# nguyenli.net
KiCad netlist of a schematic drawn in Altium Designer
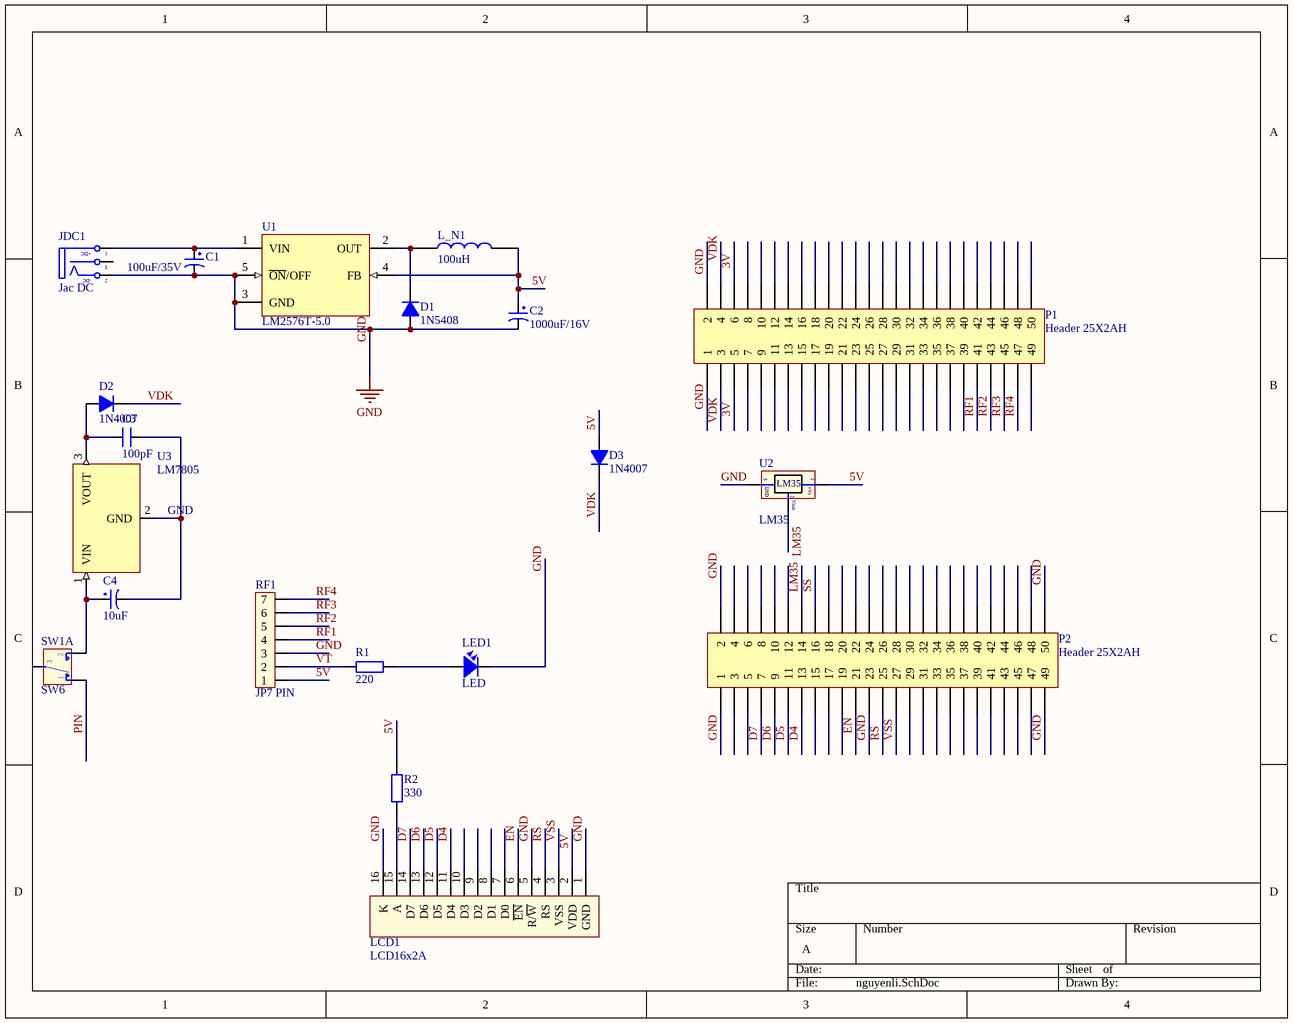
[diagram p0: nguyenli.SchDoc]

(export (version "E")
  (design (tool "Eeschema 10.0.6"))
  (components
    (comp (ref "C1")
      (value "100uF/35V")
      (footprint "CP1.5/3.4")
      (description "Cap 100uF/35V - 470uF/16V")
      (libsource (lib "syhaunguyen") (part "CP3"))
    )
    (comp (ref "C2")
      (value "1000uF/16V")
      (footprint "CP1.5/3.4")
      (description "Cap 1000uF/16V - 220uF/50V")
      (libsource (lib "syhaunguyen") (part "CP4"))
    )
    (comp (ref "C3")
      (value "100pF")
      (footprint "CN1")
      (description "Cap np  1pF - 472pF")
      (libsource (lib "Cty1") (part "CN1"))
    )
    (comp (ref "C4")
      (value "10uF")
      (footprint "CP1/2")
      (description "Cap P  0,1uF < 22uF , 16 - 50V")
      (libsource (lib "Cty1") (part "CP1"))
    )
    (comp (ref "D1")
      (value "1N5408")
      (footprint "D5A")
      (description "Diode 5A")
      (libsource (lib "syhaunguyen") (part "D5A"))
    )
    (comp (ref "D2")
      (value "1N4007")
      (footprint "D1A")
      (description "Diode 1A")
      (libsource (lib "Cty1") (part "D1A"))
    )
    (comp (ref "D3")
      (value "1N4007")
      (footprint "D1A")
      (description "Diode 1A")
      (libsource (lib "Cty1") (part "D1A"))
    )
    (comp (ref "JDC1")
      (value "Jac DC")
      (footprint "DC-IN")
      (description "Jac DC input")
      (libsource (lib "Cty1") (part "DCIN"))
    )
    (comp (ref "LCD1")
      (value "LCD16x2A")
      (footprint "LCD16X2")
      (description "LCD dipslay 16 char, 2 line")
      (libsource (lib "Cty1") (part "LCD16x2"))
    )
    (comp (ref "LED1")
      (value "LED")
      (footprint "LED-3")
      (description "LED Single colour Green and Red")
      (libsource (lib "syhaunguyen") (part "LED"))
    )
    (comp (ref "L_N1") (value "100uH") (footprint "100UH") (libsource (lib "Cty1") (part "INDUCTOR1")))
    (comp (ref "P1")
      (value "Header 25X2AH")
      (footprint "HDR2X25")
      (description "Header, 25-Pin, Dual row")
      (fields (field (name "PUBLISHER") "Altium Limited"))
      (libsource (lib "Cty1") (part "Header 25X2AH"))
    )
    (comp (ref "P2")
      (value "Header 25X2AH")
      (footprint "HDR2X25")
      (description "Header, 25-Pin, Dual row")
      (fields (field (name "PUBLISHER") "Altium Limited"))
      (libsource (lib "Cty1") (part "Header 25X2AH"))
    )
    (comp (ref "R1")
      (value "220")
      (footprint "R1/4W")
      (description "Resistor 1/4W")
      (libsource (lib "Cty1") (part "R1/4W"))
    )
    (comp (ref "R2")
      (value "330")
      (footprint "R1/4W")
      (description "Resistor 1/4W")
      (libsource (lib "Cty1") (part "R1/4W"))
    )
    (comp (ref "RF1") (value "JP7 PIN") (footprint "JP7") (libsource (lib "Cty1") (part "JP7")))
    (comp (ref "SW1")
      (value "SW6")
      (footprint "SW6")
      (description "SW-DTDP - 6 Pin")
      (libsource (lib "Cty1") (part "SW6"))
    )
    (comp (ref "U1")
      (value "LM2576T-5.0")
      (footprint "LM2576t")
      (description "SIMPLE SWITCHER; 3A Step-Down Voltage Regulator")
      (fields
        (field (name "MANUFACTURER") "National Semiconductor")
        (field (name "DIGIKEYPARTNUMBER") "LM2576T-5.0-ND")
        (field (name "PUBLISHER") "Altium Limited")
      )
      (libsource (lib "Cty1") (part "LM2576T-5.0"))
    )
    (comp (ref "U2")
      (value "LM35")
      (footprint "QTO-92")
      (description "Teminal")
      (libsource (lib "Cty1") (part "LM35"))
    )
    (comp (ref "U3")
      (value "LM7805")
      (footprint "QTO-220H3")
      (description "TO-220")
      (libsource (lib "Cty1") (part "LM7805"))
    )
  )
  (nets
    (net (code "1") (name "/3V") (class "Default")
      (node (ref "P1") (pin "5") (pinfunction "5_5") (pintype "passive"))
      (node (ref "P1") (pin "6") (pinfunction "6_6") (pintype "passive"))
    )
    (net (code "2") (name "/5V") (class "Default")
      (node (ref "C2") (pin "1") (pinfunction "1_1") (pintype "passive"))
      (node (ref "D3") (pin "1") (pinfunction "A_1") (pintype "passive"))
      (node (ref "LCD1") (pin "2") (pinfunction "VDD_2") (pintype "passive"))
      (node (ref "L_N1") (pin "2") (pinfunction "2_2") (pintype "passive"))
      (node (ref "R2") (pin "2") (pinfunction "2_2") (pintype "passive"))
      (node (ref "RF1") (pin "1") (pinfunction "1_1") (pintype "passive"))
      (node (ref "U1") (pin "4") (pinfunction "FB_4") (pintype "input"))
      (node (ref "U2") (pin "1") (pinfunction "+Vs_1") (pintype "passive"))
    )
    (net (code "3") (name "/D4") (class "Default")
      (node (ref "LCD1") (pin "11") (pinfunction "D4_11") (pintype "passive"))
      (node (ref "P2") (pin "13") (pinfunction "13_13") (pintype "passive"))
    )
    (net (code "4") (name "/D5") (class "Default")
      (node (ref "LCD1") (pin "12") (pinfunction "D5_12") (pintype "passive"))
      (node (ref "P2") (pin "11") (pinfunction "11_11") (pintype "passive"))
    )
    (net (code "5") (name "/D6") (class "Default")
      (node (ref "LCD1") (pin "13") (pinfunction "D6_13") (pintype "passive"))
      (node (ref "P2") (pin "9") (pinfunction "9_9") (pintype "passive"))
    )
    (net (code "6") (name "/D7") (class "Default")
      (node (ref "LCD1") (pin "14") (pinfunction "D7_14") (pintype "passive"))
      (node (ref "P2") (pin "7") (pinfunction "7_7") (pintype "passive"))
    )
    (net (code "7") (name "/EN") (class "Default")
      (node (ref "LCD1") (pin "6") (pinfunction "~{EN}_6") (pintype "passive"))
      (node (ref "P2") (pin "21") (pinfunction "21_21") (pintype "passive"))
    )
    (net (code "8") (name "/LM35") (class "Default")
      (node (ref "P2") (pin "14") (pinfunction "14_14") (pintype "passive"))
      (node (ref "U2") (pin "2") (pinfunction "Vout_2") (pintype "passive"))
    )
    (net (code "9") (name "/PIN") (class "Default")
      (node (ref "SW1") (pin "1") (pinfunction "1_1") (pintype "passive"))
    )
    (net (code "10") (name "/RF1") (class "Default")
      (node (ref "P1") (pin "41") (pinfunction "41_41") (pintype "passive"))
      (node (ref "RF1") (pin "4") (pinfunction "4_4") (pintype "passive"))
    )
    (net (code "11") (name "/RF2") (class "Default")
      (node (ref "P1") (pin "43") (pinfunction "43_43") (pintype "passive"))
      (node (ref "RF1") (pin "5") (pinfunction "5_5") (pintype "passive"))
    )
    (net (code "12") (name "/RF3") (class "Default")
      (node (ref "P1") (pin "45") (pinfunction "45_45") (pintype "passive"))
      (node (ref "RF1") (pin "6") (pinfunction "6_6") (pintype "passive"))
    )
    (net (code "13") (name "/RF4") (class "Default")
      (node (ref "P1") (pin "47") (pinfunction "47_47") (pintype "passive"))
      (node (ref "RF1") (pin "7") (pinfunction "7_7") (pintype "passive"))
    )
    (net (code "14") (name "/RS") (class "Default")
      (node (ref "LCD1") (pin "4") (pinfunction "RS_4") (pintype "passive"))
      (node (ref "P2") (pin "25") (pinfunction "25_25") (pintype "passive"))
    )
    (net (code "15") (name "/SS") (class "Default")
      (node (ref "P2") (pin "16") (pinfunction "16_16") (pintype "passive"))
    )
    (net (code "16") (name "/VDK") (class "Default")
      (node (ref "D2") (pin "2") (pinfunction "K_2") (pintype "passive"))
      (node (ref "D3") (pin "2") (pinfunction "K_2") (pintype "passive"))
      (node (ref "P1") (pin "3") (pinfunction "3_3") (pintype "passive"))
      (node (ref "P1") (pin "4") (pinfunction "4_4") (pintype "passive"))
    )
    (net (code "17") (name "/VSS") (class "Default")
      (node (ref "LCD1") (pin "3") (pinfunction "VSS_3") (pintype "passive"))
      (node (ref "P2") (pin "27") (pinfunction "27_27") (pintype "passive"))
    )
    (net (code "18") (name "/VT") (class "Default")
      (node (ref "R1") (pin "2") (pinfunction "2_2") (pintype "passive"))
      (node (ref "RF1") (pin "2") (pinfunction "2_2") (pintype "passive"))
    )
    (net (code "19") (name "GND") (class "Default")
      (node (ref "C1") (pin "2") (pinfunction "2_2") (pintype "passive"))
      (node (ref "C2") (pin "2") (pinfunction "2_2") (pintype "passive"))
      (node (ref "D1") (pin "1") (pinfunction "A_1") (pintype "passive"))
      (node (ref "JDC1") (pin "2") (pinfunction "TN_2") (pintype "passive"))
      (node (ref "LCD1") (pin "1") (pinfunction "GND_1") (pintype "passive"))
      (node (ref "LCD1") (pin "16") (pinfunction "K_16") (pintype "passive"))
      (node (ref "LCD1") (pin "5") (pinfunction "R/~{W}_5") (pintype "passive"))
      (node (ref "LED1") (pin "2") (pinfunction "2_2") (pintype "passive"))
      (node (ref "P1") (pin "1") (pinfunction "1_1") (pintype "passive"))
      (node (ref "P1") (pin "2") (pinfunction "2_2") (pintype "passive"))
      (node (ref "P2") (pin "1") (pinfunction "1_1") (pintype "passive"))
      (node (ref "P2") (pin "2") (pinfunction "2_2") (pintype "passive"))
      (node (ref "P2") (pin "23") (pinfunction "23_23") (pintype "passive"))
      (node (ref "P2") (pin "49") (pinfunction "49_49") (pintype "passive"))
      (node (ref "P2") (pin "50") (pinfunction "50_50") (pintype "passive"))
      (node (ref "RF1") (pin "3") (pinfunction "3_3") (pintype "passive"))
      (node (ref "U1") (pin "3") (pinfunction "GND_3") (pintype "power_in"))
      (node (ref "U1") (pin "5") (pinfunction "~{ON}/OFF_5") (pintype "input"))
      (node (ref "U2") (pin "3") (pinfunction "-_3") (pintype "passive"))
    )
    (net (code "20") (name "Net-(D1-K)") (class "Default")
      (node (ref "D1") (pin "2") (pinfunction "K_2") (pintype "passive"))
      (node (ref "L_N1") (pin "1") (pinfunction "1_1") (pintype "passive"))
      (node (ref "U1") (pin "2") (pinfunction "OUT_2") (pintype "power_in"))
    )
    (net (code "21") (name "Net-(D2-A)") (class "Default")
      (node (ref "C3") (pin "1") (pinfunction "1_1") (pintype "passive"))
      (node (ref "D2") (pin "1") (pinfunction "A_1") (pintype "passive"))
      (node (ref "U3") (pin "3") (pinfunction "VOUT_3") (pintype "output"))
    )
    (net (code "22") (name "Net-(JDC1-T)") (class "Default")
      (node (ref "C1") (pin "1") (pinfunction "1_1") (pintype "passive"))
      (node (ref "JDC1") (pin "1") (pinfunction "T_1") (pintype "passive"))
      (node (ref "U1") (pin "1") (pinfunction "VIN_1") (pintype "power_in"))
    )
    (net (code "23") (name "Net-(LCD1-A)") (class "Default")
      (node (ref "LCD1") (pin "15") (pinfunction "A_15") (pintype "passive"))
      (node (ref "R2") (pin "1") (pinfunction "1_1") (pintype "passive"))
    )
    (net (code "24") (name "Net-(LED1-Pad1)") (class "Default")
      (node (ref "LED1") (pin "1") (pinfunction "1_1") (pintype "passive"))
      (node (ref "R1") (pin "1") (pinfunction "1_1") (pintype "passive"))
    )
    (net (code "25") (name "Net-(U3-GND)") (class "Default")
      (node (ref "C3") (pin "2") (pinfunction "2_2") (pintype "passive"))
      (node (ref "C4") (pin "2") (pinfunction "2_2") (pintype "passive"))
      (node (ref "U3") (pin "2") (pinfunction "GND_2") (pintype "power_in"))
    )
    (net (code "26") (name "Net-(U3-VIN)") (class "Default")
      (node (ref "C4") (pin "1") (pinfunction "1_1") (pintype "passive"))
      (node (ref "SW1") (pin "2") (pinfunction "2_2") (pintype "passive"))
      (node (ref "U3") (pin "1") (pinfunction "VIN_1") (pintype "input"))
    )
    (net (code "27") (name "unconnected-(JDC1-S-Pad3)") (class "Default")
      (node (ref "JDC1") (pin "3") (pinfunction "S_3") (pintype "power_in"))
    )
    (net (code "28") (name "unconnected-(LCD1-D0-Pad7)") (class "Default")
      (node (ref "LCD1") (pin "7") (pinfunction "D0_7") (pintype "passive"))
    )
    (net (code "29") (name "unconnected-(LCD1-D1-Pad8)") (class "Default")
      (node (ref "LCD1") (pin "8") (pinfunction "D1_8") (pintype "passive"))
    )
    (net (code "30") (name "unconnected-(LCD1-D2-Pad9)") (class "Default")
      (node (ref "LCD1") (pin "9") (pinfunction "D2_9") (pintype "passive"))
    )
    (net (code "31") (name "unconnected-(LCD1-D3-Pad10)") (class "Default")
      (node (ref "LCD1") (pin "10") (pinfunction "D3_10") (pintype "passive"))
    )
    (net (code "32") (name "unconnected-(P1-Pad7)") (class "Default")
      (node (ref "P1") (pin "7") (pinfunction "7_7") (pintype "passive"))
    )
    (net (code "33") (name "unconnected-(P1-Pad8)") (class "Default")
      (node (ref "P1") (pin "8") (pinfunction "8_8") (pintype "passive"))
    )
    (net (code "34") (name "unconnected-(P1-Pad9)") (class "Default")
      (node (ref "P1") (pin "9") (pinfunction "9_9") (pintype "passive"))
    )
    (net (code "35") (name "unconnected-(P1-Pad10)") (class "Default")
      (node (ref "P1") (pin "10") (pinfunction "10_10") (pintype "passive"))
    )
    (net (code "36") (name "unconnected-(P1-Pad11)") (class "Default")
      (node (ref "P1") (pin "11") (pinfunction "11_11") (pintype "passive"))
    )
    (net (code "37") (name "unconnected-(P1-Pad12)") (class "Default")
      (node (ref "P1") (pin "12") (pinfunction "12_12") (pintype "passive"))
    )
    (net (code "38") (name "unconnected-(P1-Pad13)") (class "Default")
      (node (ref "P1") (pin "13") (pinfunction "13_13") (pintype "passive"))
    )
    (net (code "39") (name "unconnected-(P1-Pad14)") (class "Default")
      (node (ref "P1") (pin "14") (pinfunction "14_14") (pintype "passive"))
    )
    (net (code "40") (name "unconnected-(P1-Pad15)") (class "Default")
      (node (ref "P1") (pin "15") (pinfunction "15_15") (pintype "passive"))
    )
    (net (code "41") (name "unconnected-(P1-Pad16)") (class "Default")
      (node (ref "P1") (pin "16") (pinfunction "16_16") (pintype "passive"))
    )
    (net (code "42") (name "unconnected-(P1-Pad17)") (class "Default")
      (node (ref "P1") (pin "17") (pinfunction "17_17") (pintype "passive"))
    )
    (net (code "43") (name "unconnected-(P1-Pad18)") (class "Default")
      (node (ref "P1") (pin "18") (pinfunction "18_18") (pintype "passive"))
    )
    (net (code "44") (name "unconnected-(P1-Pad19)") (class "Default")
      (node (ref "P1") (pin "19") (pinfunction "19_19") (pintype "passive"))
    )
    (net (code "45") (name "unconnected-(P1-Pad20)") (class "Default")
      (node (ref "P1") (pin "20") (pinfunction "20_20") (pintype "passive"))
    )
    (net (code "46") (name "unconnected-(P1-Pad21)") (class "Default")
      (node (ref "P1") (pin "21") (pinfunction "21_21") (pintype "passive"))
    )
    (net (code "47") (name "unconnected-(P1-Pad22)") (class "Default")
      (node (ref "P1") (pin "22") (pinfunction "22_22") (pintype "passive"))
    )
    (net (code "48") (name "unconnected-(P1-Pad23)") (class "Default")
      (node (ref "P1") (pin "23") (pinfunction "23_23") (pintype "passive"))
    )
    (net (code "49") (name "unconnected-(P1-Pad24)") (class "Default")
      (node (ref "P1") (pin "24") (pinfunction "24_24") (pintype "passive"))
    )
    (net (code "50") (name "unconnected-(P1-Pad25)") (class "Default")
      (node (ref "P1") (pin "25") (pinfunction "25_25") (pintype "passive"))
    )
    (net (code "51") (name "unconnected-(P1-Pad26)") (class "Default")
      (node (ref "P1") (pin "26") (pinfunction "26_26") (pintype "passive"))
    )
    (net (code "52") (name "unconnected-(P1-Pad27)") (class "Default")
      (node (ref "P1") (pin "27") (pinfunction "27_27") (pintype "passive"))
    )
    (net (code "53") (name "unconnected-(P1-Pad28)") (class "Default")
      (node (ref "P1") (pin "28") (pinfunction "28_28") (pintype "passive"))
    )
    (net (code "54") (name "unconnected-(P1-Pad29)") (class "Default")
      (node (ref "P1") (pin "29") (pinfunction "29_29") (pintype "passive"))
    )
    (net (code "55") (name "unconnected-(P1-Pad30)") (class "Default")
      (node (ref "P1") (pin "30") (pinfunction "30_30") (pintype "passive"))
    )
    (net (code "56") (name "unconnected-(P1-Pad31)") (class "Default")
      (node (ref "P1") (pin "31") (pinfunction "31_31") (pintype "passive"))
    )
    (net (code "57") (name "unconnected-(P1-Pad32)") (class "Default")
      (node (ref "P1") (pin "32") (pinfunction "32_32") (pintype "passive"))
    )
    (net (code "58") (name "unconnected-(P1-Pad33)") (class "Default")
      (node (ref "P1") (pin "33") (pinfunction "33_33") (pintype "passive"))
    )
    (net (code "59") (name "unconnected-(P1-Pad34)") (class "Default")
      (node (ref "P1") (pin "34") (pinfunction "34_34") (pintype "passive"))
    )
    (net (code "60") (name "unconnected-(P1-Pad35)") (class "Default")
      (node (ref "P1") (pin "35") (pinfunction "35_35") (pintype "passive"))
    )
    (net (code "61") (name "unconnected-(P1-Pad36)") (class "Default")
      (node (ref "P1") (pin "36") (pinfunction "36_36") (pintype "passive"))
    )
    (net (code "62") (name "unconnected-(P1-Pad37)") (class "Default")
      (node (ref "P1") (pin "37") (pinfunction "37_37") (pintype "passive"))
    )
    (net (code "63") (name "unconnected-(P1-Pad38)") (class "Default")
      (node (ref "P1") (pin "38") (pinfunction "38_38") (pintype "passive"))
    )
    (net (code "64") (name "unconnected-(P1-Pad39)") (class "Default")
      (node (ref "P1") (pin "39") (pinfunction "39_39") (pintype "passive"))
    )
    (net (code "65") (name "unconnected-(P1-Pad40)") (class "Default")
      (node (ref "P1") (pin "40") (pinfunction "40_40") (pintype "passive"))
    )
    (net (code "66") (name "unconnected-(P1-Pad42)") (class "Default")
      (node (ref "P1") (pin "42") (pinfunction "42_42") (pintype "passive"))
    )
    (net (code "67") (name "unconnected-(P1-Pad44)") (class "Default")
      (node (ref "P1") (pin "44") (pinfunction "44_44") (pintype "passive"))
    )
    (net (code "68") (name "unconnected-(P1-Pad46)") (class "Default")
      (node (ref "P1") (pin "46") (pinfunction "46_46") (pintype "passive"))
    )
    (net (code "69") (name "unconnected-(P1-Pad48)") (class "Default")
      (node (ref "P1") (pin "48") (pinfunction "48_48") (pintype "passive"))
    )
    (net (code "70") (name "unconnected-(P1-Pad49)") (class "Default")
      (node (ref "P1") (pin "49") (pinfunction "49_49") (pintype "passive"))
    )
    (net (code "71") (name "unconnected-(P1-Pad50)") (class "Default")
      (node (ref "P1") (pin "50") (pinfunction "50_50") (pintype "passive"))
    )
    (net (code "72") (name "unconnected-(P2-Pad3)") (class "Default")
      (node (ref "P2") (pin "3") (pinfunction "3_3") (pintype "passive"))
    )
    (net (code "73") (name "unconnected-(P2-Pad4)") (class "Default")
      (node (ref "P2") (pin "4") (pinfunction "4_4") (pintype "passive"))
    )
    (net (code "74") (name "unconnected-(P2-Pad5)") (class "Default")
      (node (ref "P2") (pin "5") (pinfunction "5_5") (pintype "passive"))
    )
    (net (code "75") (name "unconnected-(P2-Pad6)") (class "Default")
      (node (ref "P2") (pin "6") (pinfunction "6_6") (pintype "passive"))
    )
    (net (code "76") (name "unconnected-(P2-Pad8)") (class "Default")
      (node (ref "P2") (pin "8") (pinfunction "8_8") (pintype "passive"))
    )
    (net (code "77") (name "unconnected-(P2-Pad10)") (class "Default")
      (node (ref "P2") (pin "10") (pinfunction "10_10") (pintype "passive"))
    )
    (net (code "78") (name "unconnected-(P2-Pad12)") (class "Default")
      (node (ref "P2") (pin "12") (pinfunction "12_12") (pintype "passive"))
    )
    (net (code "79") (name "unconnected-(P2-Pad15)") (class "Default")
      (node (ref "P2") (pin "15") (pinfunction "15_15") (pintype "passive"))
    )
    (net (code "80") (name "unconnected-(P2-Pad17)") (class "Default")
      (node (ref "P2") (pin "17") (pinfunction "17_17") (pintype "passive"))
    )
    (net (code "81") (name "unconnected-(P2-Pad18)") (class "Default")
      (node (ref "P2") (pin "18") (pinfunction "18_18") (pintype "passive"))
    )
    (net (code "82") (name "unconnected-(P2-Pad19)") (class "Default")
      (node (ref "P2") (pin "19") (pinfunction "19_19") (pintype "passive"))
    )
    (net (code "83") (name "unconnected-(P2-Pad20)") (class "Default")
      (node (ref "P2") (pin "20") (pinfunction "20_20") (pintype "passive"))
    )
    (net (code "84") (name "unconnected-(P2-Pad22)") (class "Default")
      (node (ref "P2") (pin "22") (pinfunction "22_22") (pintype "passive"))
    )
    (net (code "85") (name "unconnected-(P2-Pad24)") (class "Default")
      (node (ref "P2") (pin "24") (pinfunction "24_24") (pintype "passive"))
    )
    (net (code "86") (name "unconnected-(P2-Pad26)") (class "Default")
      (node (ref "P2") (pin "26") (pinfunction "26_26") (pintype "passive"))
    )
    (net (code "87") (name "unconnected-(P2-Pad28)") (class "Default")
      (node (ref "P2") (pin "28") (pinfunction "28_28") (pintype "passive"))
    )
    (net (code "88") (name "unconnected-(P2-Pad29)") (class "Default")
      (node (ref "P2") (pin "29") (pinfunction "29_29") (pintype "passive"))
    )
    (net (code "89") (name "unconnected-(P2-Pad30)") (class "Default")
      (node (ref "P2") (pin "30") (pinfunction "30_30") (pintype "passive"))
    )
    (net (code "90") (name "unconnected-(P2-Pad31)") (class "Default")
      (node (ref "P2") (pin "31") (pinfunction "31_31") (pintype "passive"))
    )
    (net (code "91") (name "unconnected-(P2-Pad32)") (class "Default")
      (node (ref "P2") (pin "32") (pinfunction "32_32") (pintype "passive"))
    )
    (net (code "92") (name "unconnected-(P2-Pad33)") (class "Default")
      (node (ref "P2") (pin "33") (pinfunction "33_33") (pintype "passive"))
    )
    (net (code "93") (name "unconnected-(P2-Pad34)") (class "Default")
      (node (ref "P2") (pin "34") (pinfunction "34_34") (pintype "passive"))
    )
    (net (code "94") (name "unconnected-(P2-Pad35)") (class "Default")
      (node (ref "P2") (pin "35") (pinfunction "35_35") (pintype "passive"))
    )
    (net (code "95") (name "unconnected-(P2-Pad36)") (class "Default")
      (node (ref "P2") (pin "36") (pinfunction "36_36") (pintype "passive"))
    )
    (net (code "96") (name "unconnected-(P2-Pad37)") (class "Default")
      (node (ref "P2") (pin "37") (pinfunction "37_37") (pintype "passive"))
    )
    (net (code "97") (name "unconnected-(P2-Pad38)") (class "Default")
      (node (ref "P2") (pin "38") (pinfunction "38_38") (pintype "passive"))
    )
    (net (code "98") (name "unconnected-(P2-Pad39)") (class "Default")
      (node (ref "P2") (pin "39") (pinfunction "39_39") (pintype "passive"))
    )
    (net (code "99") (name "unconnected-(P2-Pad40)") (class "Default")
      (node (ref "P2") (pin "40") (pinfunction "40_40") (pintype "passive"))
    )
    (net (code "100") (name "unconnected-(P2-Pad41)") (class "Default")
      (node (ref "P2") (pin "41") (pinfunction "41_41") (pintype "passive"))
    )
    (net (code "101") (name "unconnected-(P2-Pad42)") (class "Default")
      (node (ref "P2") (pin "42") (pinfunction "42_42") (pintype "passive"))
    )
    (net (code "102") (name "unconnected-(P2-Pad43)") (class "Default")
      (node (ref "P2") (pin "43") (pinfunction "43_43") (pintype "passive"))
    )
    (net (code "103") (name "unconnected-(P2-Pad44)") (class "Default")
      (node (ref "P2") (pin "44") (pinfunction "44_44") (pintype "passive"))
    )
    (net (code "104") (name "unconnected-(P2-Pad45)") (class "Default")
      (node (ref "P2") (pin "45") (pinfunction "45_45") (pintype "passive"))
    )
    (net (code "105") (name "unconnected-(P2-Pad46)") (class "Default")
      (node (ref "P2") (pin "46") (pinfunction "46_46") (pintype "passive"))
    )
    (net (code "106") (name "unconnected-(P2-Pad47)") (class "Default")
      (node (ref "P2") (pin "47") (pinfunction "47_47") (pintype "passive"))
    )
    (net (code "107") (name "unconnected-(P2-Pad48)") (class "Default")
      (node (ref "P2") (pin "48") (pinfunction "48_48") (pintype "passive"))
    )
    (net (code "108") (name "unconnected-(SW1-Pad3)") (class "Default")
      (node (ref "SW1") (pin "3") (pinfunction "3_3") (pintype "passive"))
    )
  )
)
